# Raspberry_PI_Servo_Hat_v1.net
KiCad netlist of a schematic drawn in EAGLE
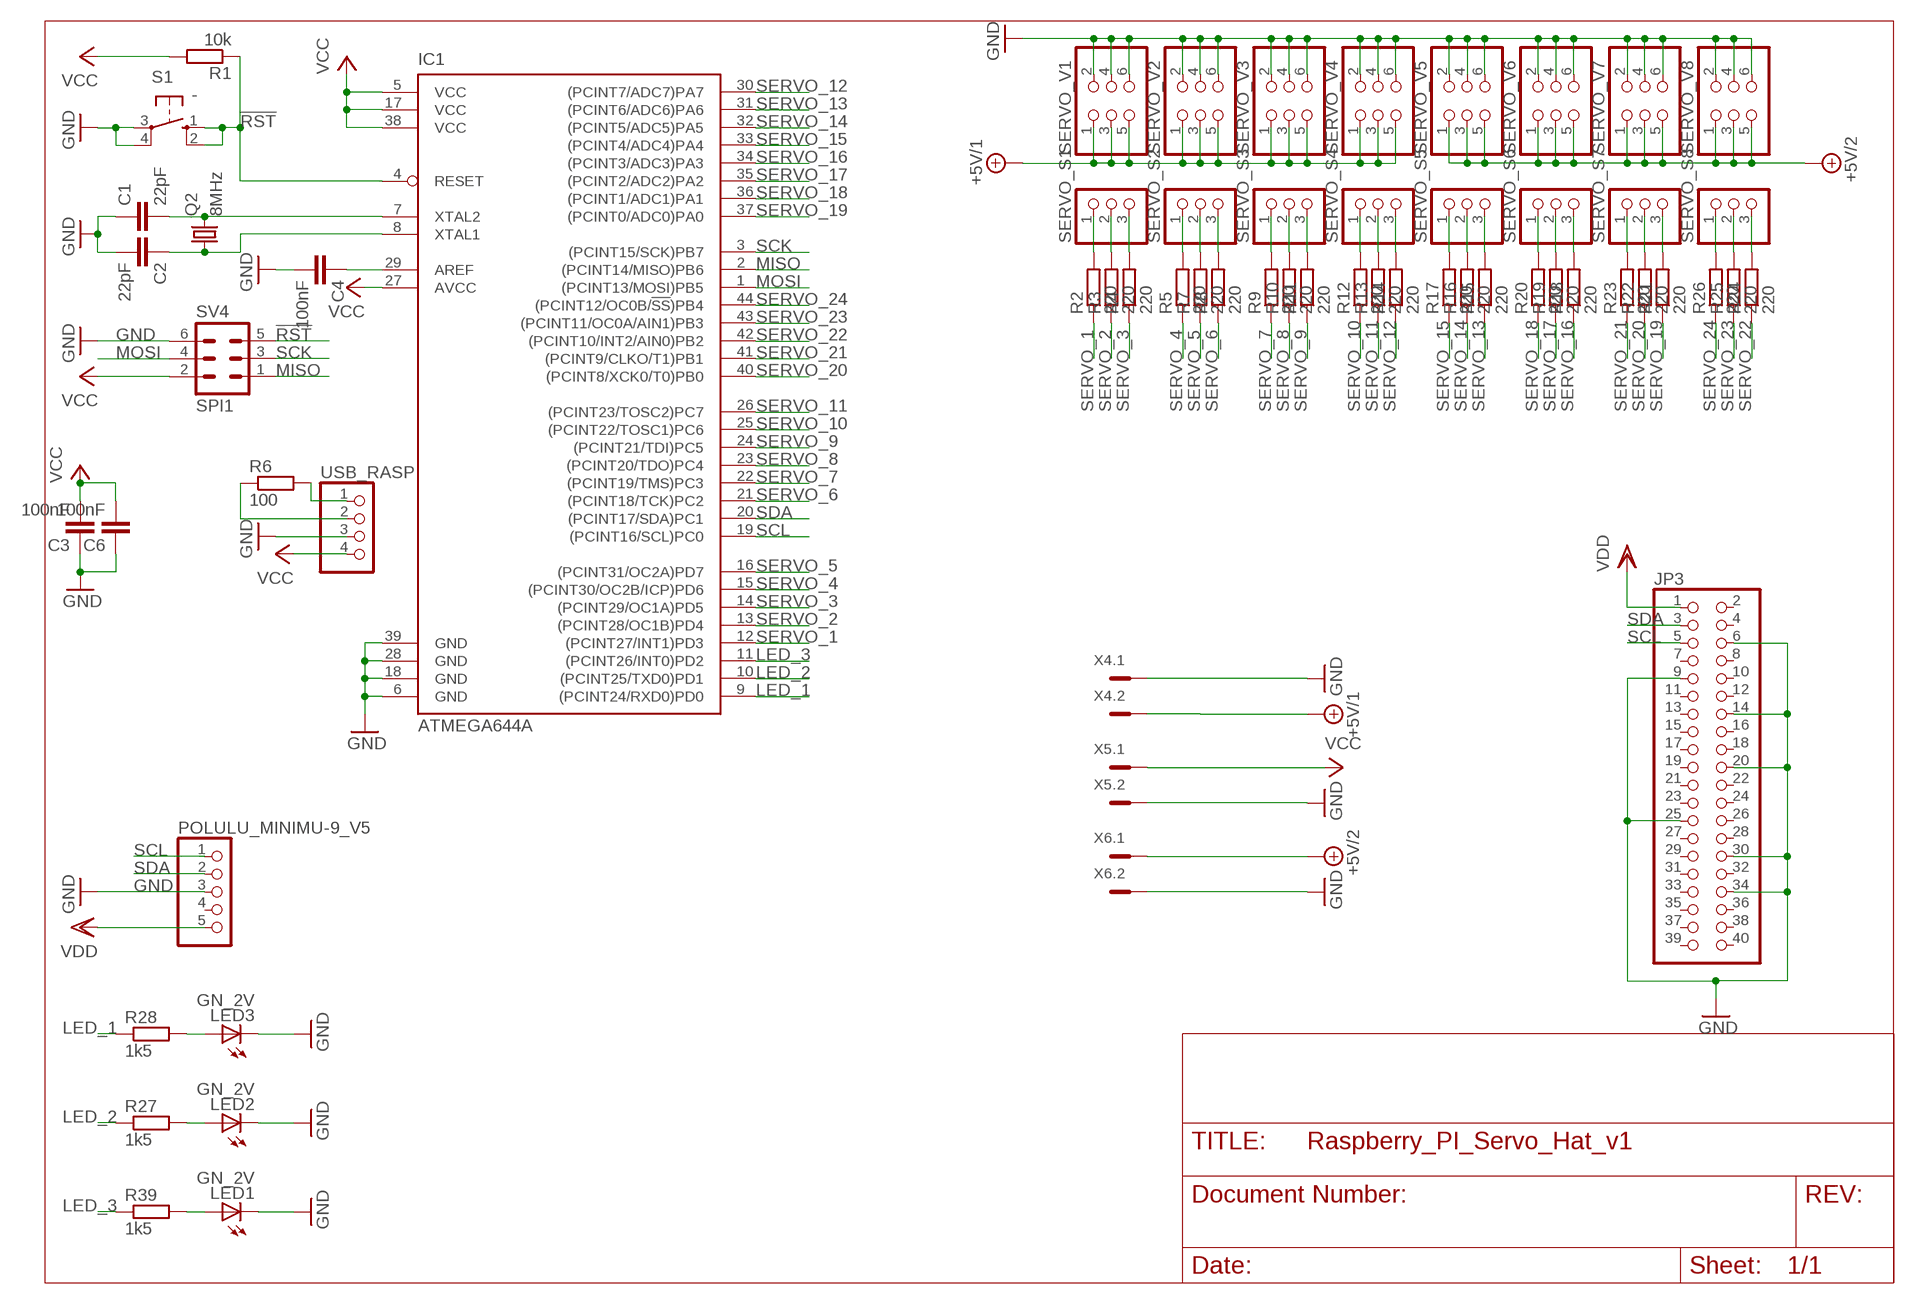
[diagram p0: schematic, sheet 1]

(export (version "E")
  (design (tool "Eeschema 10.0.6"))
  (components
    (comp (ref "C1")
      (value "22pF")
      (footprint "eagle-import:C0805")
      (libsource (lib "eagle-import") (part "C-EUC0805"))
    )
    (comp (ref "C2")
      (value "22pF")
      (footprint "eagle-import:C0805")
      (libsource (lib "eagle-import") (part "C-EUC0805"))
    )
    (comp (ref "C3")
      (value "100nF")
      (footprint "eagle-import:C0805")
      (libsource (lib "eagle-import") (part "resistor_C-EUC0805"))
    )
    (comp (ref "C4")
      (value "100nF")
      (footprint "eagle-import:C0805")
      (libsource (lib "eagle-import") (part "resistor_C-EUC0805"))
    )
    (comp (ref "C6")
      (value "100nF")
      (footprint "eagle-import:C0805")
      (libsource (lib "eagle-import") (part "resistor_C-EUC0805"))
    )
    (comp (ref "IC1")
      (value "ATMEGA644A")
      (footprint "eagle-import:TQFP44")
      (fields (field (name "MPN") "ATMEGA644PV-10AU"))
      (libsource (lib "eagle-import") (part "ATMEGA644A"))
    )
    (comp (ref "JP3")
      (value "PINHD-2X20")
      (footprint "eagle-import:2X20")
      (libsource (lib "eagle-import") (part "PINHD-2X20"))
    )
    (comp (ref "LED1")
      (value "GN_2V")
      (footprint "eagle-import:LED3MM")
      (libsource (lib "eagle-import") (part "LED3MM"))
    )
    (comp (ref "LED2")
      (value "GN_2V")
      (footprint "eagle-import:LED3MM")
      (libsource (lib "eagle-import") (part "LED3MM"))
    )
    (comp (ref "LED3")
      (value "GN_2V")
      (footprint "eagle-import:LED3MM")
      (libsource (lib "eagle-import") (part "LED3MM"))
    )
    (comp (ref "POLULU_MINIMU-9_V5")
      (value "PINHD-1X5")
      (footprint "eagle-import:1X05")
      (libsource (lib "eagle-import") (part "PINHD-1X5"))
    )
    (comp (ref "Q2")
      (value "8MHz")
      (footprint "eagle-import:HC49U-V")
      (libsource (lib "eagle-import") (part "CRYSTALHC49U-V"))
    )
    (comp (ref "R1")
      (value "10k")
      (footprint "eagle-import:R0805")
      (libsource (lib "eagle-import") (part "resistor_R-EU_R0805"))
    )
    (comp (ref "R2")
      (value "220")
      (footprint "eagle-import:R0805")
      (libsource (lib "eagle-import") (part "resistor_R-EU_R0805"))
    )
    (comp (ref "R3")
      (value "220")
      (footprint "eagle-import:R0805")
      (libsource (lib "eagle-import") (part "resistor_R-EU_R0805"))
    )
    (comp (ref "R4")
      (value "220")
      (footprint "eagle-import:R0805")
      (libsource (lib "eagle-import") (part "resistor_R-EU_R0805"))
    )
    (comp (ref "R5")
      (value "220")
      (footprint "eagle-import:R0805")
      (libsource (lib "eagle-import") (part "resistor_R-EU_R0805"))
    )
    (comp (ref "R6")
      (value "100")
      (footprint "eagle-import:R0805")
      (libsource (lib "eagle-import") (part "R-EU_R0805"))
    )
    (comp (ref "R7")
      (value "220")
      (footprint "eagle-import:R0805")
      (libsource (lib "eagle-import") (part "resistor_R-EU_R0805"))
    )
    (comp (ref "R8")
      (value "220")
      (footprint "eagle-import:R0805")
      (libsource (lib "eagle-import") (part "resistor_R-EU_R0805"))
    )
    (comp (ref "R9")
      (value "220")
      (footprint "eagle-import:R0805")
      (libsource (lib "eagle-import") (part "resistor_R-EU_R0805"))
    )
    (comp (ref "R10")
      (value "220")
      (footprint "eagle-import:R0805")
      (libsource (lib "eagle-import") (part "resistor_R-EU_R0805"))
    )
    (comp (ref "R11")
      (value "220")
      (footprint "eagle-import:R0805")
      (libsource (lib "eagle-import") (part "resistor_R-EU_R0805"))
    )
    (comp (ref "R12")
      (value "220")
      (footprint "eagle-import:R0805")
      (libsource (lib "eagle-import") (part "resistor_R-EU_R0805"))
    )
    (comp (ref "R13")
      (value "220")
      (footprint "eagle-import:R0805")
      (libsource (lib "eagle-import") (part "resistor_R-EU_R0805"))
    )
    (comp (ref "R14")
      (value "220")
      (footprint "eagle-import:R0805")
      (libsource (lib "eagle-import") (part "resistor_R-EU_R0805"))
    )
    (comp (ref "R15")
      (value "220")
      (footprint "eagle-import:R0805")
      (libsource (lib "eagle-import") (part "resistor_R-EU_R0805"))
    )
    (comp (ref "R16")
      (value "220")
      (footprint "eagle-import:R0805")
      (libsource (lib "eagle-import") (part "resistor_R-EU_R0805"))
    )
    (comp (ref "R17")
      (value "220")
      (footprint "eagle-import:R0805")
      (libsource (lib "eagle-import") (part "resistor_R-EU_R0805"))
    )
    (comp (ref "R18")
      (value "220")
      (footprint "eagle-import:R0805")
      (libsource (lib "eagle-import") (part "resistor_R-EU_R0805"))
    )
    (comp (ref "R19")
      (value "220")
      (footprint "eagle-import:R0805")
      (libsource (lib "eagle-import") (part "resistor_R-EU_R0805"))
    )
    (comp (ref "R20")
      (value "220")
      (footprint "eagle-import:R0805")
      (libsource (lib "eagle-import") (part "resistor_R-EU_R0805"))
    )
    (comp (ref "R21")
      (value "220")
      (footprint "eagle-import:R0805")
      (libsource (lib "eagle-import") (part "resistor_R-EU_R0805"))
    )
    (comp (ref "R22")
      (value "220")
      (footprint "eagle-import:R0805")
      (libsource (lib "eagle-import") (part "resistor_R-EU_R0805"))
    )
    (comp (ref "R23")
      (value "220")
      (footprint "eagle-import:R0805")
      (libsource (lib "eagle-import") (part "resistor_R-EU_R0805"))
    )
    (comp (ref "R24")
      (value "220")
      (footprint "eagle-import:R0805")
      (libsource (lib "eagle-import") (part "resistor_R-EU_R0805"))
    )
    (comp (ref "R25")
      (value "220")
      (footprint "eagle-import:R0805")
      (libsource (lib "eagle-import") (part "resistor_R-EU_R0805"))
    )
    (comp (ref "R26")
      (value "220")
      (footprint "eagle-import:R0805")
      (libsource (lib "eagle-import") (part "resistor_R-EU_R0805"))
    )
    (comp (ref "R27")
      (value "1k5")
      (footprint "eagle-import:R0805")
      (libsource (lib "eagle-import") (part "R-EU_R0805"))
    )
    (comp (ref "R28")
      (value "1k5")
      (footprint "eagle-import:R0805")
      (libsource (lib "eagle-import") (part "R-EU_R0805"))
    )
    (comp (ref "R39")
      (value "1k5")
      (footprint "eagle-import:R0805")
      (libsource (lib "eagle-import") (part "R-EU_R0805"))
    )
    (comp (ref "S1")
      (value "-")
      (footprint "eagle-import:B3F-10XX")
      (fields (field (name "MPN") "B3F-1000"))
      (libsource (lib "eagle-import") (part "10-XX"))
    )
    (comp (ref "SERVO_S1")
      (value "PINHD-1X3")
      (footprint "eagle-import:1X03")
      (libsource (lib "eagle-import") (part "PINHD-1X3"))
    )
    (comp (ref "SERVO_S2")
      (value "PINHD-1X3")
      (footprint "eagle-import:1X03")
      (libsource (lib "eagle-import") (part "PINHD-1X3"))
    )
    (comp (ref "SERVO_S3")
      (value "PINHD-1X3")
      (footprint "eagle-import:1X03")
      (libsource (lib "eagle-import") (part "PINHD-1X3"))
    )
    (comp (ref "SERVO_S4")
      (value "PINHD-1X3")
      (footprint "eagle-import:1X03")
      (libsource (lib "eagle-import") (part "PINHD-1X3"))
    )
    (comp (ref "SERVO_S5")
      (value "PINHD-1X3")
      (footprint "eagle-import:1X03")
      (libsource (lib "eagle-import") (part "PINHD-1X3"))
    )
    (comp (ref "SERVO_S6")
      (value "PINHD-1X3")
      (footprint "eagle-import:1X03")
      (libsource (lib "eagle-import") (part "PINHD-1X3"))
    )
    (comp (ref "SERVO_S7")
      (value "PINHD-1X3")
      (footprint "eagle-import:1X03")
      (libsource (lib "eagle-import") (part "PINHD-1X3"))
    )
    (comp (ref "SERVO_S8")
      (value "PINHD-1X3")
      (footprint "eagle-import:1X03")
      (libsource (lib "eagle-import") (part "PINHD-1X3"))
    )
    (comp (ref "SERVO_V1")
      (value "PINHD-2X3")
      (footprint "eagle-import:2X03")
      (libsource (lib "eagle-import") (part "PINHD-2X3"))
    )
    (comp (ref "SERVO_V2")
      (value "PINHD-2X3")
      (footprint "eagle-import:2X03")
      (libsource (lib "eagle-import") (part "PINHD-2X3"))
    )
    (comp (ref "SERVO_V3")
      (value "PINHD-2X3")
      (footprint "eagle-import:2X03")
      (libsource (lib "eagle-import") (part "PINHD-2X3"))
    )
    (comp (ref "SERVO_V4")
      (value "PINHD-2X3")
      (footprint "eagle-import:2X03")
      (libsource (lib "eagle-import") (part "PINHD-2X3"))
    )
    (comp (ref "SERVO_V5")
      (value "PINHD-2X3")
      (footprint "eagle-import:2X03")
      (libsource (lib "eagle-import") (part "PINHD-2X3"))
    )
    (comp (ref "SERVO_V6")
      (value "PINHD-2X3")
      (footprint "eagle-import:2X03")
      (libsource (lib "eagle-import") (part "PINHD-2X3"))
    )
    (comp (ref "SERVO_V7")
      (value "PINHD-2X3")
      (footprint "eagle-import:2X03")
      (libsource (lib "eagle-import") (part "PINHD-2X3"))
    )
    (comp (ref "SERVO_V8")
      (value "PINHD-2X3")
      (footprint "eagle-import:2X03")
      (libsource (lib "eagle-import") (part "PINHD-2X3"))
    )
    (comp (ref "SV4")
      (value "SPI1")
      (footprint "eagle-import:ML6")
      (libsource (lib "eagle-import") (part "ML6"))
    )
    (comp (ref "USB_RASP")
      (value "PINHD-1X4")
      (footprint "eagle-import:1X04")
      (libsource (lib "eagle-import") (part "PINHD-1X4"))
    )
    (comp (ref "X4")
      (value "MCV2")
      (footprint "eagle-import:MCV2")
      (libsource (lib "eagle-import") (part "MCV2"))
    )
    (comp (ref "X5")
      (value "MCV2")
      (footprint "eagle-import:MCV2")
      (libsource (lib "eagle-import") (part "MCV2"))
    )
    (comp (ref "X6")
      (value "MCV2")
      (footprint "eagle-import:MCV2")
      (libsource (lib "eagle-import") (part "MCV2"))
    )
  )
  (nets
    (net (code "1") (name "+5V{slash}1") (class "Default")
      (node (ref "SERVO_V1") (pin "1") (pinfunction "1_1") (pintype "passive"))
      (node (ref "SERVO_V1") (pin "3") (pinfunction "3_3") (pintype "passive"))
      (node (ref "SERVO_V1") (pin "5") (pinfunction "5_5") (pintype "passive"))
      (node (ref "SERVO_V2") (pin "1") (pinfunction "1_1") (pintype "passive"))
      (node (ref "SERVO_V2") (pin "3") (pinfunction "3_3") (pintype "passive"))
      (node (ref "SERVO_V2") (pin "5") (pinfunction "5_5") (pintype "passive"))
      (node (ref "SERVO_V3") (pin "1") (pinfunction "1_1") (pintype "passive"))
      (node (ref "SERVO_V3") (pin "3") (pinfunction "3_3") (pintype "passive"))
      (node (ref "SERVO_V3") (pin "5") (pinfunction "5_5") (pintype "passive"))
      (node (ref "SERVO_V4") (pin "1") (pinfunction "1_1") (pintype "passive"))
      (node (ref "SERVO_V4") (pin "3") (pinfunction "3_3") (pintype "passive"))
      (node (ref "SERVO_V4") (pin "5") (pinfunction "5_5") (pintype "passive"))
      (node (ref "X4") (pin "2") (pinfunction "SK_2") (pintype "passive"))
    )
    (net (code "2") (name "+5V{slash}2") (class "Default")
      (node (ref "SERVO_V5") (pin "1") (pinfunction "1_1") (pintype "passive"))
      (node (ref "SERVO_V5") (pin "3") (pinfunction "3_3") (pintype "passive"))
      (node (ref "SERVO_V5") (pin "5") (pinfunction "5_5") (pintype "passive"))
      (node (ref "SERVO_V6") (pin "1") (pinfunction "1_1") (pintype "passive"))
      (node (ref "SERVO_V6") (pin "3") (pinfunction "3_3") (pintype "passive"))
      (node (ref "SERVO_V6") (pin "5") (pinfunction "5_5") (pintype "passive"))
      (node (ref "SERVO_V7") (pin "1") (pinfunction "1_1") (pintype "passive"))
      (node (ref "SERVO_V7") (pin "3") (pinfunction "3_3") (pintype "passive"))
      (node (ref "SERVO_V7") (pin "5") (pinfunction "5_5") (pintype "passive"))
      (node (ref "SERVO_V8") (pin "1") (pinfunction "1_1") (pintype "passive"))
      (node (ref "SERVO_V8") (pin "3") (pinfunction "3_3") (pintype "passive"))
      (node (ref "SERVO_V8") (pin "5") (pinfunction "5_5") (pintype "passive"))
      (node (ref "X6") (pin "1") (pinfunction "SK_1") (pintype "passive"))
    )
    (net (code "3") (name "/LED_1") (class "Default")
      (node (ref "IC1") (pin "9") (pinfunction "(PCINT24/RXD0)PD0_9") (pintype "bidirectional"))
      (node (ref "R28") (pin "1") (pinfunction "1_1") (pintype "passive"))
    )
    (net (code "4") (name "/LED_2") (class "Default")
      (node (ref "IC1") (pin "10") (pinfunction "(PCINT25/TXD0)PD1_10") (pintype "bidirectional"))
      (node (ref "R27") (pin "1") (pinfunction "1_1") (pintype "passive"))
    )
    (net (code "5") (name "/LED_3") (class "Default")
      (node (ref "IC1") (pin "11") (pinfunction "(PCINT26/INT0)PD2_11") (pintype "bidirectional"))
      (node (ref "R39") (pin "1") (pinfunction "1_1") (pintype "passive"))
    )
    (net (code "6") (name "/MISO") (class "Default")
      (node (ref "IC1") (pin "2") (pinfunction "(PCINT14/MISO)PB6_2") (pintype "bidirectional"))
      (node (ref "SV4") (pin "1") (pinfunction "1_1") (pintype "passive"))
    )
    (net (code "7") (name "/MOSI") (class "Default")
      (node (ref "IC1") (pin "1") (pinfunction "(PCINT13/MOSI)PB5_1") (pintype "bidirectional"))
      (node (ref "SV4") (pin "4") (pinfunction "4_4") (pintype "passive"))
    )
    (net (code "8") (name "/SCK") (class "Default")
      (node (ref "IC1") (pin "3") (pinfunction "(PCINT15/SCK)PB7_3") (pintype "bidirectional"))
      (node (ref "SV4") (pin "3") (pinfunction "3_3") (pintype "passive"))
    )
    (net (code "9") (name "/SCL") (class "Default")
      (node (ref "IC1") (pin "19") (pinfunction "(PCINT16/SCL)PC0_19") (pintype "output"))
      (node (ref "JP3") (pin "5") (pinfunction "5_5") (pintype "passive"))
      (node (ref "POLULU_MINIMU-9_V5") (pin "1") (pinfunction "1_1") (pintype "passive"))
    )
    (net (code "10") (name "/SDA") (class "Default")
      (node (ref "IC1") (pin "20") (pinfunction "(PCINT17/SDA)PC1_20") (pintype "output"))
      (node (ref "JP3") (pin "3") (pinfunction "3_3") (pintype "passive"))
      (node (ref "POLULU_MINIMU-9_V5") (pin "2") (pinfunction "2_2") (pintype "passive"))
    )
    (net (code "11") (name "/SERVO_1") (class "Default")
      (node (ref "IC1") (pin "12") (pinfunction "(PCINT27/INT1)PD3_12") (pintype "bidirectional"))
      (node (ref "R2") (pin "1") (pinfunction "1_1") (pintype "passive"))
    )
    (net (code "12") (name "/SERVO_2") (class "Default")
      (node (ref "IC1") (pin "13") (pinfunction "(PCINT28/OC1B)PD4_13") (pintype "bidirectional"))
      (node (ref "R3") (pin "1") (pinfunction "1_1") (pintype "passive"))
    )
    (net (code "13") (name "/SERVO_3") (class "Default")
      (node (ref "IC1") (pin "14") (pinfunction "(PCINT29/OC1A)PD5_14") (pintype "bidirectional"))
      (node (ref "R4") (pin "1") (pinfunction "1_1") (pintype "passive"))
    )
    (net (code "14") (name "/SERVO_4") (class "Default")
      (node (ref "IC1") (pin "15") (pinfunction "(PCINT30/OC2B/ICP)PD6_15") (pintype "bidirectional"))
      (node (ref "R5") (pin "1") (pinfunction "1_1") (pintype "passive"))
    )
    (net (code "15") (name "/SERVO_5") (class "Default")
      (node (ref "IC1") (pin "16") (pinfunction "(PCINT31/OC2A)PD7_16") (pintype "bidirectional"))
      (node (ref "R7") (pin "1") (pinfunction "1_1") (pintype "passive"))
    )
    (net (code "16") (name "/SERVO_6") (class "Default")
      (node (ref "IC1") (pin "21") (pinfunction "(PCINT18/TCK)PC2_21") (pintype "output"))
      (node (ref "R8") (pin "1") (pinfunction "1_1") (pintype "passive"))
    )
    (net (code "17") (name "/SERVO_7") (class "Default")
      (node (ref "IC1") (pin "22") (pinfunction "(PCINT19/TMS)PC3_22") (pintype "output"))
      (node (ref "R9") (pin "1") (pinfunction "1_1") (pintype "passive"))
    )
    (net (code "18") (name "/SERVO_8") (class "Default")
      (node (ref "IC1") (pin "23") (pinfunction "(PCINT20/TDO)PC4_23") (pintype "output"))
      (node (ref "R10") (pin "1") (pinfunction "1_1") (pintype "passive"))
    )
    (net (code "19") (name "/SERVO_9") (class "Default")
      (node (ref "IC1") (pin "24") (pinfunction "(PCINT21/TDI)PC5_24") (pintype "output"))
      (node (ref "R11") (pin "1") (pinfunction "1_1") (pintype "passive"))
    )
    (net (code "20") (name "/SERVO_10") (class "Default")
      (node (ref "IC1") (pin "25") (pinfunction "(PCINT22/TOSC1)PC6_25") (pintype "output"))
      (node (ref "R12") (pin "1") (pinfunction "1_1") (pintype "passive"))
    )
    (net (code "21") (name "/SERVO_11") (class "Default")
      (node (ref "IC1") (pin "26") (pinfunction "(PCINT23/TOSC2)PC7_26") (pintype "output"))
      (node (ref "R13") (pin "1") (pinfunction "1_1") (pintype "passive"))
    )
    (net (code "22") (name "/SERVO_12") (class "Default")
      (node (ref "IC1") (pin "30") (pinfunction "(PCINT7/ADC7)PA7_30") (pintype "bidirectional"))
      (node (ref "R14") (pin "1") (pinfunction "1_1") (pintype "passive"))
    )
    (net (code "23") (name "/SERVO_13") (class "Default")
      (node (ref "IC1") (pin "31") (pinfunction "(PCINT6/ADC6)PA6_31") (pintype "bidirectional"))
      (node (ref "R15") (pin "1") (pinfunction "1_1") (pintype "passive"))
    )
    (net (code "24") (name "/SERVO_14") (class "Default")
      (node (ref "IC1") (pin "32") (pinfunction "(PCINT5/ADC5)PA5_32") (pintype "bidirectional"))
      (node (ref "R16") (pin "1") (pinfunction "1_1") (pintype "passive"))
    )
    (net (code "25") (name "/SERVO_15") (class "Default")
      (node (ref "IC1") (pin "33") (pinfunction "(PCINT4/ADC4)PA4_33") (pintype "bidirectional"))
      (node (ref "R17") (pin "1") (pinfunction "1_1") (pintype "passive"))
    )
    (net (code "26") (name "/SERVO_16") (class "Default")
      (node (ref "IC1") (pin "34") (pinfunction "(PCINT3/ADC3)PA3_34") (pintype "bidirectional"))
      (node (ref "R18") (pin "1") (pinfunction "1_1") (pintype "passive"))
    )
    (net (code "27") (name "/SERVO_17") (class "Default")
      (node (ref "IC1") (pin "35") (pinfunction "(PCINT2/ADC2)PA2_35") (pintype "bidirectional"))
      (node (ref "R19") (pin "1") (pinfunction "1_1") (pintype "passive"))
    )
    (net (code "28") (name "/SERVO_18") (class "Default")
      (node (ref "IC1") (pin "36") (pinfunction "(PCINT1/ADC1)PA1_36") (pintype "bidirectional"))
      (node (ref "R20") (pin "1") (pinfunction "1_1") (pintype "passive"))
    )
    (net (code "29") (name "/SERVO_19") (class "Default")
      (node (ref "IC1") (pin "37") (pinfunction "(PCINT0/ADC0)PA0_37") (pintype "bidirectional"))
      (node (ref "R21") (pin "1") (pinfunction "1_1") (pintype "passive"))
    )
    (net (code "30") (name "/SERVO_20") (class "Default")
      (node (ref "IC1") (pin "40") (pinfunction "(PCINT8/XCK0/T0)PB0_40") (pintype "bidirectional"))
      (node (ref "R22") (pin "1") (pinfunction "1_1") (pintype "passive"))
    )
    (net (code "31") (name "/SERVO_21") (class "Default")
      (node (ref "IC1") (pin "41") (pinfunction "(PCINT9/CLKO/T1)PB1_41") (pintype "bidirectional"))
      (node (ref "R23") (pin "1") (pinfunction "1_1") (pintype "passive"))
    )
    (net (code "32") (name "/SERVO_22") (class "Default")
      (node (ref "IC1") (pin "42") (pinfunction "(PCINT10/INT2/AIN0)PB2_42") (pintype "bidirectional"))
      (node (ref "R24") (pin "1") (pinfunction "1_1") (pintype "passive"))
    )
    (net (code "33") (name "/SERVO_23") (class "Default")
      (node (ref "IC1") (pin "43") (pinfunction "(PCINT11/OC0A/AIN1)PB3_43") (pintype "bidirectional"))
      (node (ref "R25") (pin "1") (pinfunction "1_1") (pintype "passive"))
    )
    (net (code "34") (name "/SERVO_24") (class "Default")
      (node (ref "IC1") (pin "44") (pinfunction "(PCINT12/OC0B/~{SS})PB4_44") (pintype "bidirectional"))
      (node (ref "R26") (pin "1") (pinfunction "1_1") (pintype "passive"))
    )
    (net (code "35") (name "/~{RST}") (class "Default")
      (node (ref "IC1") (pin "4") (pinfunction "RESET_4") (pintype "input"))
      (node (ref "R1") (pin "1") (pinfunction "1_1") (pintype "passive"))
      (node (ref "S1") (pin "1") (pinfunction "S_1") (pintype "passive"))
      (node (ref "S1") (pin "2") (pinfunction "S1_2") (pintype "passive"))
      (node (ref "SV4") (pin "5") (pinfunction "5_5") (pintype "passive"))
    )
    (net (code "36") (name "GND") (class "Default")
      (node (ref "C1") (pin "1") (pinfunction "1_1") (pintype "passive"))
      (node (ref "C2") (pin "2") (pinfunction "2_2") (pintype "passive"))
      (node (ref "C3") (pin "1") (pinfunction "1_1") (pintype "passive"))
      (node (ref "C4") (pin "2") (pinfunction "2_2") (pintype "passive"))
      (node (ref "C6") (pin "1") (pinfunction "1_1") (pintype "passive"))
      (node (ref "IC1") (pin "18") (pinfunction "GND_18") (pintype "power_in"))
      (node (ref "IC1") (pin "28") (pinfunction "GND_28") (pintype "power_in"))
      (node (ref "IC1") (pin "39") (pinfunction "GND_39") (pintype "power_in"))
      (node (ref "IC1") (pin "6") (pinfunction "GND_6") (pintype "power_in"))
      (node (ref "JP3") (pin "14") (pinfunction "14_14") (pintype "passive"))
      (node (ref "JP3") (pin "20") (pinfunction "20_20") (pintype "passive"))
      (node (ref "JP3") (pin "25") (pinfunction "25_25") (pintype "passive"))
      (node (ref "JP3") (pin "30") (pinfunction "30_30") (pintype "passive"))
      (node (ref "JP3") (pin "34") (pinfunction "34_34") (pintype "passive"))
      (node (ref "JP3") (pin "6") (pinfunction "6_6") (pintype "passive"))
      (node (ref "JP3") (pin "9") (pinfunction "9_9") (pintype "passive"))
      (node (ref "LED1") (pin "K") (pinfunction "C_K") (pintype "passive"))
      (node (ref "LED2") (pin "K") (pinfunction "C_K") (pintype "passive"))
      (node (ref "LED3") (pin "K") (pinfunction "C_K") (pintype "passive"))
      (node (ref "POLULU_MINIMU-9_V5") (pin "3") (pinfunction "3_3") (pintype "passive"))
      (node (ref "S1") (pin "3") (pinfunction "P_3") (pintype "passive"))
      (node (ref "S1") (pin "4") (pinfunction "P1_4") (pintype "passive"))
      (node (ref "SERVO_V1") (pin "2") (pinfunction "2_2") (pintype "passive"))
      (node (ref "SERVO_V1") (pin "4") (pinfunction "4_4") (pintype "passive"))
      (node (ref "SERVO_V1") (pin "6") (pinfunction "6_6") (pintype "passive"))
      (node (ref "SERVO_V2") (pin "2") (pinfunction "2_2") (pintype "passive"))
      (node (ref "SERVO_V2") (pin "4") (pinfunction "4_4") (pintype "passive"))
      (node (ref "SERVO_V2") (pin "6") (pinfunction "6_6") (pintype "passive"))
      (node (ref "SERVO_V3") (pin "2") (pinfunction "2_2") (pintype "passive"))
      (node (ref "SERVO_V3") (pin "4") (pinfunction "4_4") (pintype "passive"))
      (node (ref "SERVO_V3") (pin "6") (pinfunction "6_6") (pintype "passive"))
      (node (ref "SERVO_V4") (pin "2") (pinfunction "2_2") (pintype "passive"))
      (node (ref "SERVO_V4") (pin "4") (pinfunction "4_4") (pintype "passive"))
      (node (ref "SERVO_V4") (pin "6") (pinfunction "6_6") (pintype "passive"))
      (node (ref "SERVO_V5") (pin "2") (pinfunction "2_2") (pintype "passive"))
      (node (ref "SERVO_V5") (pin "4") (pinfunction "4_4") (pintype "passive"))
      (node (ref "SERVO_V5") (pin "6") (pinfunction "6_6") (pintype "passive"))
      (node (ref "SERVO_V6") (pin "2") (pinfunction "2_2") (pintype "passive"))
      (node (ref "SERVO_V6") (pin "4") (pinfunction "4_4") (pintype "passive"))
      (node (ref "SERVO_V6") (pin "6") (pinfunction "6_6") (pintype "passive"))
      (node (ref "SERVO_V7") (pin "2") (pinfunction "2_2") (pintype "passive"))
      (node (ref "SERVO_V7") (pin "4") (pinfunction "4_4") (pintype "passive"))
      (node (ref "SERVO_V7") (pin "6") (pinfunction "6_6") (pintype "passive"))
      (node (ref "SERVO_V8") (pin "2") (pinfunction "2_2") (pintype "passive"))
      (node (ref "SERVO_V8") (pin "4") (pinfunction "4_4") (pintype "passive"))
      (node (ref "SERVO_V8") (pin "6") (pinfunction "6_6") (pintype "passive"))
      (node (ref "SV4") (pin "6") (pinfunction "6_6") (pintype "passive"))
      (node (ref "USB_RASP") (pin "3") (pinfunction "3_3") (pintype "passive"))
      (node (ref "X4") (pin "1") (pinfunction "SK_1") (pintype "passive"))
      (node (ref "X5") (pin "2") (pinfunction "SK_2") (pintype "passive"))
      (node (ref "X6") (pin "2") (pinfunction "SK_2") (pintype "passive"))
    )
    (net (code "37") (name "Net-(IC1-AREF)") (class "Default")
      (node (ref "C4") (pin "1") (pinfunction "1_1") (pintype "passive"))
      (node (ref "IC1") (pin "29") (pinfunction "AREF_29") (pintype "passive"))
    )
    (net (code "38") (name "Net-(IC1-XTAL1)") (class "Default")
      (node (ref "C2") (pin "1") (pinfunction "1_1") (pintype "passive"))
      (node (ref "IC1") (pin "8") (pinfunction "XTAL1_8") (pintype "bidirectional"))
      (node (ref "Q2") (pin "1") (pinfunction "1_1") (pintype "passive"))
    )
    (net (code "39") (name "Net-(IC1-XTAL2)") (class "Default")
      (node (ref "C1") (pin "2") (pinfunction "2_2") (pintype "passive"))
      (node (ref "IC1") (pin "7") (pinfunction "XTAL2_7") (pintype "bidirectional"))
      (node (ref "Q2") (pin "2") (pinfunction "2_2") (pintype "passive"))
    )
    (net (code "40") (name "Net-(LED1-PadA)") (class "Default")
      (node (ref "LED1") (pin "A") (pinfunction "A_A") (pintype "passive"))
      (node (ref "R39") (pin "2") (pinfunction "2_2") (pintype "passive"))
    )
    (net (code "41") (name "Net-(LED2-PadA)") (class "Default")
      (node (ref "LED2") (pin "A") (pinfunction "A_A") (pintype "passive"))
      (node (ref "R27") (pin "2") (pinfunction "2_2") (pintype "passive"))
    )
    (net (code "42") (name "Net-(LED3-PadA)") (class "Default")
      (node (ref "LED3") (pin "A") (pinfunction "A_A") (pintype "passive"))
      (node (ref "R28") (pin "2") (pinfunction "2_2") (pintype "passive"))
    )
    (net (code "43") (name "Net-(R2-Pad2)") (class "Default")
      (node (ref "R2") (pin "2") (pinfunction "2_2") (pintype "passive"))
      (node (ref "SERVO_S1") (pin "1") (pinfunction "1_1") (pintype "passive"))
    )
    (net (code "44") (name "Net-(R3-Pad2)") (class "Default")
      (node (ref "R3") (pin "2") (pinfunction "2_2") (pintype "passive"))
      (node (ref "SERVO_S1") (pin "2") (pinfunction "2_2") (pintype "passive"))
    )
    (net (code "45") (name "Net-(R4-Pad2)") (class "Default")
      (node (ref "R4") (pin "2") (pinfunction "2_2") (pintype "passive"))
      (node (ref "SERVO_S1") (pin "3") (pinfunction "3_3") (pintype "passive"))
    )
    (net (code "46") (name "Net-(R5-Pad2)") (class "Default")
      (node (ref "R5") (pin "2") (pinfunction "2_2") (pintype "passive"))
      (node (ref "SERVO_S2") (pin "1") (pinfunction "1_1") (pintype "passive"))
    )
    (net (code "47") (name "Net-(R6-Pad1)") (class "Default")
      (node (ref "R6") (pin "1") (pinfunction "1_1") (pintype "passive"))
      (node (ref "USB_RASP") (pin "2") (pinfunction "2_2") (pintype "passive"))
    )
    (net (code "48") (name "Net-(R6-Pad2)") (class "Default")
      (node (ref "R6") (pin "2") (pinfunction "2_2") (pintype "passive"))
      (node (ref "USB_RASP") (pin "1") (pinfunction "1_1") (pintype "passive"))
    )
    (net (code "49") (name "Net-(R7-Pad2)") (class "Default")
      (node (ref "R7") (pin "2") (pinfunction "2_2") (pintype "passive"))
      (node (ref "SERVO_S2") (pin "2") (pinfunction "2_2") (pintype "passive"))
    )
    (net (code "50") (name "Net-(R8-Pad2)") (class "Default")
      (node (ref "R8") (pin "2") (pinfunction "2_2") (pintype "passive"))
      (node (ref "SERVO_S2") (pin "3") (pinfunction "3_3") (pintype "passive"))
    )
    (net (code "51") (name "Net-(R9-Pad2)") (class "Default")
      (node (ref "R9") (pin "2") (pinfunction "2_2") (pintype "passive"))
      (node (ref "SERVO_S3") (pin "1") (pinfunction "1_1") (pintype "passive"))
    )
    (net (code "52") (name "Net-(R10-Pad2)") (class "Default")
      (node (ref "R10") (pin "2") (pinfunction "2_2") (pintype "passive"))
      (node (ref "SERVO_S3") (pin "2") (pinfunction "2_2") (pintype "passive"))
    )
    (net (code "53") (name "Net-(R11-Pad2)") (class "Default")
      (node (ref "R11") (pin "2") (pinfunction "2_2") (pintype "passive"))
      (node (ref "SERVO_S3") (pin "3") (pinfunction "3_3") (pintype "passive"))
    )
    (net (code "54") (name "Net-(R12-Pad2)") (class "Default")
      (node (ref "R12") (pin "2") (pinfunction "2_2") (pintype "passive"))
      (node (ref "SERVO_S4") (pin "1") (pinfunction "1_1") (pintype "passive"))
    )
    (net (code "55") (name "Net-(R13-Pad2)") (class "Default")
      (node (ref "R13") (pin "2") (pinfunction "2_2") (pintype "passive"))
      (node (ref "SERVO_S4") (pin "2") (pinfunction "2_2") (pintype "passive"))
    )
    (net (code "56") (name "Net-(R14-Pad2)") (class "Default")
      (node (ref "R14") (pin "2") (pinfunction "2_2") (pintype "passive"))
      (node (ref "SERVO_S4") (pin "3") (pinfunction "3_3") (pintype "passive"))
    )
    (net (code "57") (name "Net-(R15-Pad2)") (class "Default")
      (node (ref "R15") (pin "2") (pinfunction "2_2") (pintype "passive"))
      (node (ref "SERVO_S5") (pin "3") (pinfunction "3_3") (pintype "passive"))
    )
    (net (code "58") (name "Net-(R16-Pad2)") (class "Default")
      (node (ref "R16") (pin "2") (pinfunction "2_2") (pintype "passive"))
      (node (ref "SERVO_S5") (pin "2") (pinfunction "2_2") (pintype "passive"))
    )
    (net (code "59") (name "Net-(R17-Pad2)") (class "Default")
      (node (ref "R17") (pin "2") (pinfunction "2_2") (pintype "passive"))
      (node (ref "SERVO_S5") (pin "1") (pinfunction "1_1") (pintype "passive"))
    )
    (net (code "60") (name "Net-(R18-Pad2)") (class "Default")
      (node (ref "R18") (pin "2") (pinfunction "2_2") (pintype "passive"))
      (node (ref "SERVO_S6") (pin "3") (pinfunction "3_3") (pintype "passive"))
    )
    (net (code "61") (name "Net-(R19-Pad2)") (class "Default")
      (node (ref "R19") (pin "2") (pinfunction "2_2") (pintype "passive"))
      (node (ref "SERVO_S6") (pin "2") (pinfunction "2_2") (pintype "passive"))
    )
    (net (code "62") (name "Net-(R20-Pad2)") (class "Default")
      (node (ref "R20") (pin "2") (pinfunction "2_2") (pintype "passive"))
      (node (ref "SERVO_S6") (pin "1") (pinfunction "1_1") (pintype "passive"))
    )
    (net (code "63") (name "Net-(R21-Pad2)") (class "Default")
      (node (ref "R21") (pin "2") (pinfunction "2_2") (pintype "passive"))
      (node (ref "SERVO_S7") (pin "3") (pinfunction "3_3") (pintype "passive"))
    )
    (net (code "64") (name "Net-(R22-Pad2)") (class "Default")
      (node (ref "R22") (pin "2") (pinfunction "2_2") (pintype "passive"))
      (node (ref "SERVO_S7") (pin "2") (pinfunction "2_2") (pintype "passive"))
    )
    (net (code "65") (name "Net-(R23-Pad2)") (class "Default")
      (node (ref "R23") (pin "2") (pinfunction "2_2") (pintype "passive"))
      (node (ref "SERVO_S7") (pin "1") (pinfunction "1_1") (pintype "passive"))
    )
    (net (code "66") (name "Net-(R24-Pad2)") (class "Default")
      (node (ref "R24") (pin "2") (pinfunction "2_2") (pintype "passive"))
      (node (ref "SERVO_S8") (pin "3") (pinfunction "3_3") (pintype "passive"))
    )
    (net (code "67") (name "Net-(R25-Pad2)") (class "Default")
      (node (ref "R25") (pin "2") (pinfunction "2_2") (pintype "passive"))
      (node (ref "SERVO_S8") (pin "2") (pinfunction "2_2") (pintype "passive"))
    )
    (net (code "68") (name "Net-(R26-Pad2)") (class "Default")
      (node (ref "R26") (pin "2") (pinfunction "2_2") (pintype "passive"))
      (node (ref "SERVO_S8") (pin "1") (pinfunction "1_1") (pintype "passive"))
    )
    (net (code "69") (name "VCC") (class "Default")
      (node (ref "C3") (pin "2") (pinfunction "2_2") (pintype "passive"))
      (node (ref "C6") (pin "2") (pinfunction "2_2") (pintype "passive"))
      (node (ref "IC1") (pin "17") (pinfunction "VCC_17") (pintype "power_in"))
      (node (ref "IC1") (pin "27") (pinfunction "AVCC_27") (pintype "power_in"))
      (node (ref "IC1") (pin "38") (pinfunction "VCC_38") (pintype "power_in"))
      (node (ref "IC1") (pin "5") (pinfunction "VCC_5") (pintype "power_in"))
      (node (ref "R1") (pin "2") (pinfunction "2_2") (pintype "passive"))
      (node (ref "SV4") (pin "2") (pinfunction "2_2") (pintype "passive"))
      (node (ref "USB_RASP") (pin "4") (pinfunction "4_4") (pintype "passive"))
      (node (ref "X5") (pin "1") (pinfunction "SK_1") (pintype "passive"))
    )
    (net (code "70") (name "VDD") (class "Default")
      (node (ref "JP3") (pin "1") (pinfunction "1_1") (pintype "passive"))
      (node (ref "POLULU_MINIMU-9_V5") (pin "5") (pinfunction "5_5") (pintype "passive"))
    )
    (net (code "71") (name "unconnected-(JP3-Pad2)") (class "Default")
      (node (ref "JP3") (pin "2") (pinfunction "2_2") (pintype "passive"))
    )
    (net (code "72") (name "unconnected-(JP3-Pad4)") (class "Default")
      (node (ref "JP3") (pin "4") (pinfunction "4_4") (pintype "passive"))
    )
    (net (code "73") (name "unconnected-(JP3-Pad7)") (class "Default")
      (node (ref "JP3") (pin "7") (pinfunction "7_7") (pintype "passive"))
    )
    (net (code "74") (name "unconnected-(JP3-Pad8)") (class "Default")
      (node (ref "JP3") (pin "8") (pinfunction "8_8") (pintype "passive"))
    )
    (net (code "75") (name "unconnected-(JP3-Pad10)") (class "Default")
      (node (ref "JP3") (pin "10") (pinfunction "10_10") (pintype "passive"))
    )
    (net (code "76") (name "unconnected-(JP3-Pad11)") (class "Default")
      (node (ref "JP3") (pin "11") (pinfunction "11_11") (pintype "passive"))
    )
    (net (code "77") (name "unconnected-(JP3-Pad12)") (class "Default")
      (node (ref "JP3") (pin "12") (pinfunction "12_12") (pintype "passive"))
    )
    (net (code "78") (name "unconnected-(JP3-Pad13)") (class "Default")
      (node (ref "JP3") (pin "13") (pinfunction "13_13") (pintype "passive"))
    )
    (net (code "79") (name "unconnected-(JP3-Pad15)") (class "Default")
      (node (ref "JP3") (pin "15") (pinfunction "15_15") (pintype "passive"))
    )
    (net (code "80") (name "unconnected-(JP3-Pad16)") (class "Default")
      (node (ref "JP3") (pin "16") (pinfunction "16_16") (pintype "passive"))
    )
    (net (code "81") (name "unconnected-(JP3-Pad17)") (class "Default")
      (node (ref "JP3") (pin "17") (pinfunction "17_17") (pintype "passive"))
    )
    (net (code "82") (name "unconnected-(JP3-Pad18)") (class "Default")
      (node (ref "JP3") (pin "18") (pinfunction "18_18") (pintype "passive"))
    )
    (net (code "83") (name "unconnected-(JP3-Pad19)") (class "Default")
      (node (ref "JP3") (pin "19") (pinfunction "19_19") (pintype "passive"))
    )
    (net (code "84") (name "unconnected-(JP3-Pad21)") (class "Default")
      (node (ref "JP3") (pin "21") (pinfunction "21_21") (pintype "passive"))
    )
    (net (code "85") (name "unconnected-(JP3-Pad22)") (class "Default")
      (node (ref "JP3") (pin "22") (pinfunction "22_22") (pintype "passive"))
    )
    (net (code "86") (name "unconnected-(JP3-Pad23)") (class "Default")
      (node (ref "JP3") (pin "23") (pinfunction "23_23") (pintype "passive"))
    )
    (net (code "87") (name "unconnected-(JP3-Pad24)") (class "Default")
      (node (ref "JP3") (pin "24") (pinfunction "24_24") (pintype "passive"))
    )
    (net (code "88") (name "unconnected-(JP3-Pad26)") (class "Default")
      (node (ref "JP3") (pin "26") (pinfunction "26_26") (pintype "passive"))
    )
    (net (code "89") (name "unconnected-(JP3-Pad27)") (class "Default")
      (node (ref "JP3") (pin "27") (pinfunction "27_27") (pintype "passive"))
    )
    (net (code "90") (name "unconnected-(JP3-Pad28)") (class "Default")
      (node (ref "JP3") (pin "28") (pinfunction "28_28") (pintype "passive"))
    )
    (net (code "91") (name "unconnected-(JP3-Pad29)") (class "Default")
      (node (ref "JP3") (pin "29") (pinfunction "29_29") (pintype "passive"))
    )
    (net (code "92") (name "unconnected-(JP3-Pad31)") (class "Default")
      (node (ref "JP3") (pin "31") (pinfunction "31_31") (pintype "passive"))
    )
    (net (code "93") (name "unconnected-(JP3-Pad32)") (class "Default")
      (node (ref "JP3") (pin "32") (pinfunction "32_32") (pintype "passive"))
    )
    (net (code "94") (name "unconnected-(JP3-Pad33)") (class "Default")
      (node (ref "JP3") (pin "33") (pinfunction "33_33") (pintype "passive"))
    )
    (net (code "95") (name "unconnected-(JP3-Pad35)") (class "Default")
      (node (ref "JP3") (pin "35") (pinfunction "35_35") (pintype "passive"))
    )
    (net (code "96") (name "unconnected-(JP3-Pad36)") (class "Default")
      (node (ref "JP3") (pin "36") (pinfunction "36_36") (pintype "passive"))
    )
    (net (code "97") (name "unconnected-(JP3-Pad37)") (class "Default")
      (node (ref "JP3") (pin "37") (pinfunction "37_37") (pintype "passive"))
    )
    (net (code "98") (name "unconnected-(JP3-Pad38)") (class "Default")
      (node (ref "JP3") (pin "38") (pinfunction "38_38") (pintype "passive"))
    )
    (net (code "99") (name "unconnected-(JP3-Pad39)") (class "Default")
      (node (ref "JP3") (pin "39") (pinfunction "39_39") (pintype "passive"))
    )
    (net (code "100") (name "unconnected-(JP3-Pad40)") (class "Default")
      (node (ref "JP3") (pin "40") (pinfunction "40_40") (pintype "passive"))
    )
    (net (code "101") (name "unconnected-(POLULU_MINIMU-9_V5-Pad4)") (class "Default")
      (node (ref "POLULU_MINIMU-9_V5") (pin "4") (pinfunction "4_4") (pintype "passive"))
    )
  )
)
